# Inputs.net
KiCad netlist of a schematic drawn in Altium Designer
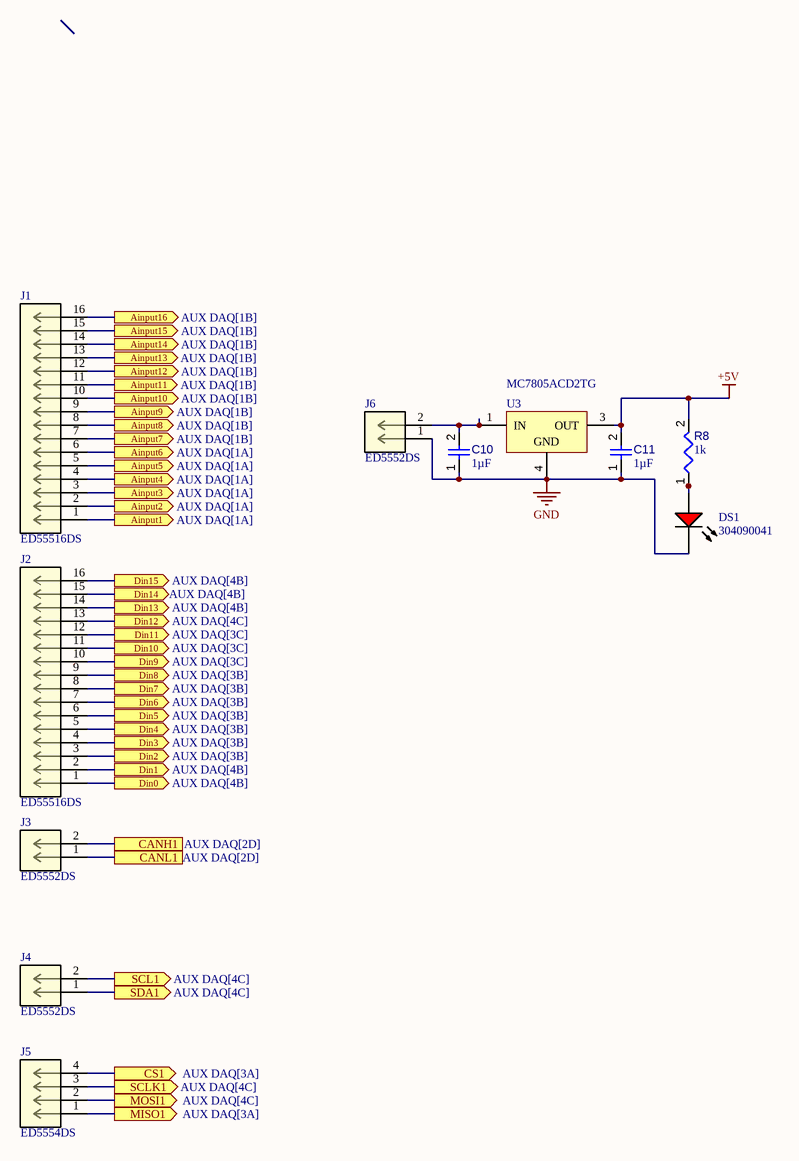
[diagram p0: Inputs.SchDoc]

(export (version "E")
  (design (tool "Eeschema 10.0.6"))
  (components
    (comp (ref "C10")
      (value "1µF")
      (footprint "CAPC3216X180X20ML20")
      (description "Chip Capacitor, 1 uF, +/- 10%, 25 V, 1206 (3216 Metric)")
      (fields (field (name "TOLERANCE") "10%") (field (name "Comment") "Capacitor 1 uF +/- 10% 25 V 1206"))
      (libsource (lib "DAQ") (part "CAP-NP-2"))
    )
    (comp (ref "C11")
      (value "1µF")
      (footprint "CAPC3216X180X20ML20")
      (description "Chip Capacitor, 1 uF, +/- 10%, 25 V, 1206 (3216 Metric)")
      (fields (field (name "TOLERANCE") "10%") (field (name "Comment") "Capacitor 1 uF +/- 10% 25 V 1206"))
      (libsource (lib "DAQ") (part "CAP-NP-2"))
    )
    (comp (ref "DS1")
      (value "304090041")
      (footprint "LED-2P-2.28-3MM_A")
      (description "Red LED, 80 mW, 30 mA, -25 to 85 degC, 2-Pin THD")
      (fields (field (name "MANUFACTURER") "Shenzhen CGX"))
      (libsource (lib "DAQ") (part "LED-RED-AK-2"))
    )
    (comp (ref "J1")
      (value "ED55516DS")
      (footprint "CONN16_ED555_56X6P5_OST")
      (description "No Description Available")
      (libsource (lib "DAQ") (part "ED55516DS"))
    )
    (comp (ref "J2")
      (value "ED55516DS")
      (footprint "CONN16_ED555_56X6P5_OST")
      (description "No Description Available")
      (libsource (lib "DAQ") (part "ED55516DS"))
    )
    (comp (ref "J3")
      (value "ED5552DS")
      (footprint "CONN_ED5552DS_OST")
      (description "No Description Available")
      (libsource (lib "DAQ") (part "ED5552DS"))
    )
    (comp (ref "J4")
      (value "ED5552DS")
      (footprint "CONN_ED5552DS_OST")
      (description "No Description Available")
      (libsource (lib "DAQ") (part "ED5552DS"))
    )
    (comp (ref "J5")
      (value "ED5554DS")
      (footprint "CONN4_ED5554DS_SHT")
      (description "No Description Available")
      (libsource (lib "DAQ") (part "ED5554DS"))
    )
    (comp (ref "J6")
      (value "ED5552DS")
      (footprint "CONN_ED5552DS_OST")
      (description "No Description Available")
      (libsource (lib "DAQ") (part "ED5552DS"))
    )
    (comp (ref "R8")
      (value "1k")
      (footprint "RESC0805(2012)_L")
      (description "Chip Resistor, 1 kOhms, +/-5%, 125 mW, -55 to 155 degC, 0805")
      (fields (field (name "TOLERANCE") "5%") (field (name "POWER") "125mW"))
      (libsource (lib "DAQ") (part "RES-2"))
    )
    (comp (ref "U3")
      (value "MC7805ACD2TG")
      (footprint "ONSC-D2PAK-3-936-03_V")
      (fields (field (name "MANUFACTURER") "ON Semiconductor"))
      (libsource (lib "DAQ") (part "ONSC-MC7805A-D2PAK-3"))
    )
  )
  (nets
    (net (code "1") (name "+5V") (class "Default")
      (node (ref "C11") (pin "2") (pinfunction "2_2") (pintype "passive"))
      (node (ref "R8") (pin "2") (pinfunction "2_2") (pintype "passive"))
      (node (ref "U3") (pin "3") (pinfunction "OUT_3") (pintype "power_in"))
    )
    (net (code "2") (name "/Ainput1") (class "Default")
      (node (ref "J1") (pin "1") (pinfunction "1_1") (pintype "passive"))
    )
    (net (code "3") (name "/Ainput2") (class "Default")
      (node (ref "J1") (pin "2") (pinfunction "2_2") (pintype "passive"))
    )
    (net (code "4") (name "/Ainput3") (class "Default")
      (node (ref "J1") (pin "3") (pinfunction "3_3") (pintype "passive"))
    )
    (net (code "5") (name "/Ainput4") (class "Default")
      (node (ref "J1") (pin "4") (pinfunction "4_4") (pintype "passive"))
    )
    (net (code "6") (name "/Ainput5") (class "Default")
      (node (ref "J1") (pin "5") (pinfunction "5_5") (pintype "passive"))
    )
    (net (code "7") (name "/Ainput6") (class "Default")
      (node (ref "J1") (pin "6") (pinfunction "6_6") (pintype "passive"))
    )
    (net (code "8") (name "/Ainput7") (class "Default")
      (node (ref "J1") (pin "7") (pinfunction "7_7") (pintype "passive"))
    )
    (net (code "9") (name "/Ainput8") (class "Default")
      (node (ref "J1") (pin "8") (pinfunction "8_8") (pintype "passive"))
    )
    (net (code "10") (name "/Ainput9") (class "Default")
      (node (ref "J1") (pin "9") (pinfunction "9_9") (pintype "passive"))
    )
    (net (code "11") (name "/Ainput10") (class "Default")
      (node (ref "J1") (pin "10") (pinfunction "10_10") (pintype "passive"))
    )
    (net (code "12") (name "/Ainput11") (class "Default")
      (node (ref "J1") (pin "11") (pinfunction "11_11") (pintype "passive"))
    )
    (net (code "13") (name "/Ainput12") (class "Default")
      (node (ref "J1") (pin "12") (pinfunction "12_12") (pintype "passive"))
    )
    (net (code "14") (name "/Ainput13") (class "Default")
      (node (ref "J1") (pin "13") (pinfunction "13_13") (pintype "passive"))
    )
    (net (code "15") (name "/Ainput14") (class "Default")
      (node (ref "J1") (pin "14") (pinfunction "14_14") (pintype "passive"))
    )
    (net (code "16") (name "/Ainput15") (class "Default")
      (node (ref "J1") (pin "15") (pinfunction "15_15") (pintype "passive"))
    )
    (net (code "17") (name "/Ainput16") (class "Default")
      (node (ref "J1") (pin "16") (pinfunction "16_16") (pintype "passive"))
    )
    (net (code "18") (name "/CANH1") (class "Default")
      (node (ref "J3") (pin "2") (pinfunction "2_2") (pintype "passive"))
    )
    (net (code "19") (name "/CANL1") (class "Default")
      (node (ref "J3") (pin "1") (pinfunction "1_1") (pintype "passive"))
    )
    (net (code "20") (name "/CS1") (class "Default")
      (node (ref "J5") (pin "4") (pinfunction "4_4") (pintype "passive"))
    )
    (net (code "21") (name "/Din0") (class "Default")
      (node (ref "J2") (pin "1") (pinfunction "1_1") (pintype "passive"))
    )
    (net (code "22") (name "/Din1") (class "Default")
      (node (ref "J2") (pin "2") (pinfunction "2_2") (pintype "passive"))
    )
    (net (code "23") (name "/Din2") (class "Default")
      (node (ref "J2") (pin "3") (pinfunction "3_3") (pintype "passive"))
    )
    (net (code "24") (name "/Din3") (class "Default")
      (node (ref "J2") (pin "4") (pinfunction "4_4") (pintype "passive"))
    )
    (net (code "25") (name "/Din4") (class "Default")
      (node (ref "J2") (pin "5") (pinfunction "5_5") (pintype "passive"))
    )
    (net (code "26") (name "/Din5") (class "Default")
      (node (ref "J2") (pin "6") (pinfunction "6_6") (pintype "passive"))
    )
    (net (code "27") (name "/Din6") (class "Default")
      (node (ref "J2") (pin "7") (pinfunction "7_7") (pintype "passive"))
    )
    (net (code "28") (name "/Din7") (class "Default")
      (node (ref "J2") (pin "8") (pinfunction "8_8") (pintype "passive"))
    )
    (net (code "29") (name "/Din8") (class "Default")
      (node (ref "J2") (pin "9") (pinfunction "9_9") (pintype "passive"))
    )
    (net (code "30") (name "/Din9") (class "Default")
      (node (ref "J2") (pin "10") (pinfunction "10_10") (pintype "passive"))
    )
    (net (code "31") (name "/Din10") (class "Default")
      (node (ref "J2") (pin "11") (pinfunction "11_11") (pintype "passive"))
    )
    (net (code "32") (name "/Din11") (class "Default")
      (node (ref "J2") (pin "12") (pinfunction "12_12") (pintype "passive"))
    )
    (net (code "33") (name "/Din12") (class "Default")
      (node (ref "J2") (pin "13") (pinfunction "13_13") (pintype "passive"))
    )
    (net (code "34") (name "/Din13") (class "Default")
      (node (ref "J2") (pin "14") (pinfunction "14_14") (pintype "passive"))
    )
    (net (code "35") (name "/Din14") (class "Default")
      (node (ref "J2") (pin "15") (pinfunction "15_15") (pintype "passive"))
    )
    (net (code "36") (name "/Din15") (class "Default")
      (node (ref "J2") (pin "16") (pinfunction "16_16") (pintype "passive"))
    )
    (net (code "37") (name "/MISO1") (class "Default")
      (node (ref "J5") (pin "1") (pinfunction "1_1") (pintype "passive"))
    )
    (net (code "38") (name "/MOSI1") (class "Default")
      (node (ref "J5") (pin "2") (pinfunction "2_2") (pintype "passive"))
    )
    (net (code "39") (name "/SCL1") (class "Default")
      (node (ref "J4") (pin "2") (pinfunction "2_2") (pintype "passive"))
    )
    (net (code "40") (name "/SCLK1") (class "Default")
      (node (ref "J5") (pin "3") (pinfunction "3_3") (pintype "passive"))
    )
    (net (code "41") (name "/SDA1") (class "Default")
      (node (ref "J4") (pin "1") (pinfunction "1_1") (pintype "passive"))
    )
    (net (code "42") (name "GND") (class "Default")
      (node (ref "C10") (pin "1") (pinfunction "1_1") (pintype "passive"))
      (node (ref "C11") (pin "1") (pinfunction "1_1") (pintype "passive"))
      (node (ref "DS1") (pin "2") (pinfunction "K_2") (pintype "passive"))
      (node (ref "J6") (pin "1") (pinfunction "1_1") (pintype "passive"))
      (node (ref "U3") (pin "4") (pinfunction "GND_4") (pintype "power_in"))
    )
    (net (code "43") (name "Net-(DS1-A)") (class "Default")
      (node (ref "DS1") (pin "1") (pinfunction "A_1") (pintype "passive"))
      (node (ref "R8") (pin "1") (pinfunction "1_1") (pintype "passive"))
    )
    (net (code "44") (name "Net-(U3-IN)") (class "Default")
      (node (ref "C10") (pin "2") (pinfunction "2_2") (pintype "passive"))
      (node (ref "J6") (pin "2") (pinfunction "2_2") (pintype "passive"))
      (node (ref "U3") (pin "1") (pinfunction "IN_1") (pintype "power_in"))
    )
  )
)
